# Fiber_interlock.net
KiCad netlist of a schematic drawn in Altium Designer
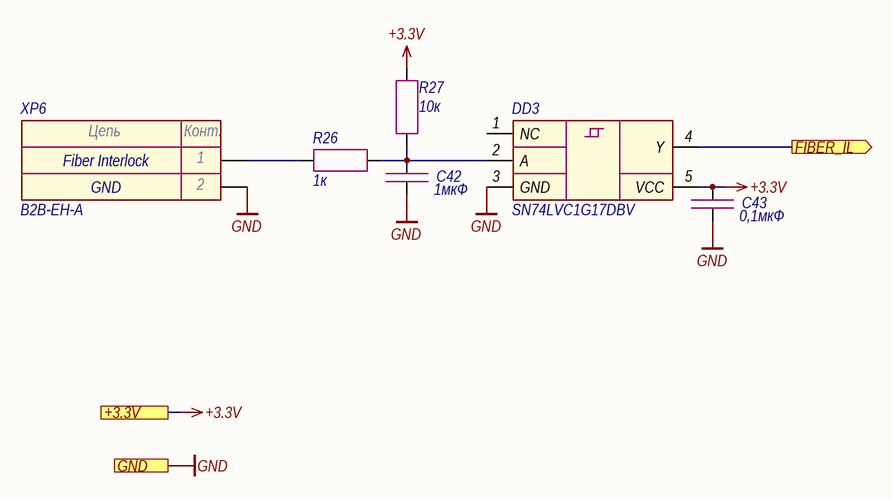
[diagram p0: Fiber_interlock.SchDoc]

(export (version "E")
  (design (tool "Eeschema 10.0.6"))
  (components
    (comp (ref "C42")
      (value "1мкФ")
      (footprint "Pcb_library:CAP_0603")
      (fields (field (name "MANUFACTURER") "Murata"))
      (libsource (lib "Schem_library") (part "Capacitor"))
    )
    (comp (ref "C43")
      (value "0,1мкФ")
      (footprint "Pcb_library:CAP_0603")
      (fields (field (name "MANUFACTURER") "Murata"))
      (libsource (lib "Schem_library") (part "Capacitor"))
    )
    (comp (ref "DD3")
      (value "SN74LVC1G17DBV")
      (footprint "Pcb_library:SOT-23-5")
      (fields (field (name "MANUFACTURER") "Texas Instruments"))
      (libsource (lib "Schem_library") (part "SN74LVC1G17"))
    )
    (comp (ref "R26")
      (value "1к")
      (footprint "Pcb_library:RES_0603")
      (fields (field (name "MANUFACTURER") "Yageo"))
      (libsource (lib "Schem_library") (part "Resistor"))
    )
    (comp (ref "R27")
      (value "10к")
      (footprint "Pcb_library:RES_0603")
      (fields (field (name "MANUFACTURER") "Yageo"))
      (libsource (lib "Schem_library") (part "Resistor"))
    )
    (comp (ref "XP6")
      (value "B2B-EH-A")
      (footprint "Pcb_library:B2B-EH-A")
      (fields (field (name "MANUFACTURER") "JST"))
      (libsource (lib "Schem_library") (part "Connector-2"))
    )
  )
  (nets
    (net (code "1") (name "+3.3V") (class "Default")
      (node (ref "C43") (pin "1") (pinfunction "1_1") (pintype "passive"))
      (node (ref "DD3") (pin "5") (pinfunction "VCC_5") (pintype "passive"))
      (node (ref "R27") (pin "2") (pinfunction "2_2") (pintype "passive"))
    )
    (net (code "2") (name "/FIBER_IL") (class "Default")
      (node (ref "DD3") (pin "4") (pinfunction "Y_4") (pintype "passive"))
    )
    (net (code "3") (name "GND") (class "Default")
      (node (ref "C42") (pin "2") (pinfunction "2_2") (pintype "passive"))
      (node (ref "C43") (pin "2") (pinfunction "2_2") (pintype "passive"))
      (node (ref "DD3") (pin "3") (pinfunction "GND_3") (pintype "passive"))
      (node (ref "XP6") (pin "2") (pintype "passive"))
    )
    (net (code "4") (name "Net-(DD3-A)") (class "Default")
      (node (ref "C42") (pin "1") (pinfunction "1_1") (pintype "passive"))
      (node (ref "DD3") (pin "2") (pinfunction "A_2") (pintype "passive"))
      (node (ref "R26") (pin "2") (pinfunction "2_2") (pintype "passive"))
      (node (ref "R27") (pin "1") (pinfunction "1_1") (pintype "passive"))
    )
    (net (code "5") (name "Net-(R26-Pad1)") (class "Default")
      (node (ref "R26") (pin "1") (pinfunction "1_1") (pintype "passive"))
      (node (ref "XP6") (pin "1") (pintype "passive"))
    )
    (net (code "6") (name "unconnected-(DD3-NC-Pad1)") (class "Default")
      (node (ref "DD3") (pin "1") (pinfunction "NC_1") (pintype "passive"))
    )
  )
)
